# Power.net
KiCad netlist of a schematic drawn in Altium Designer
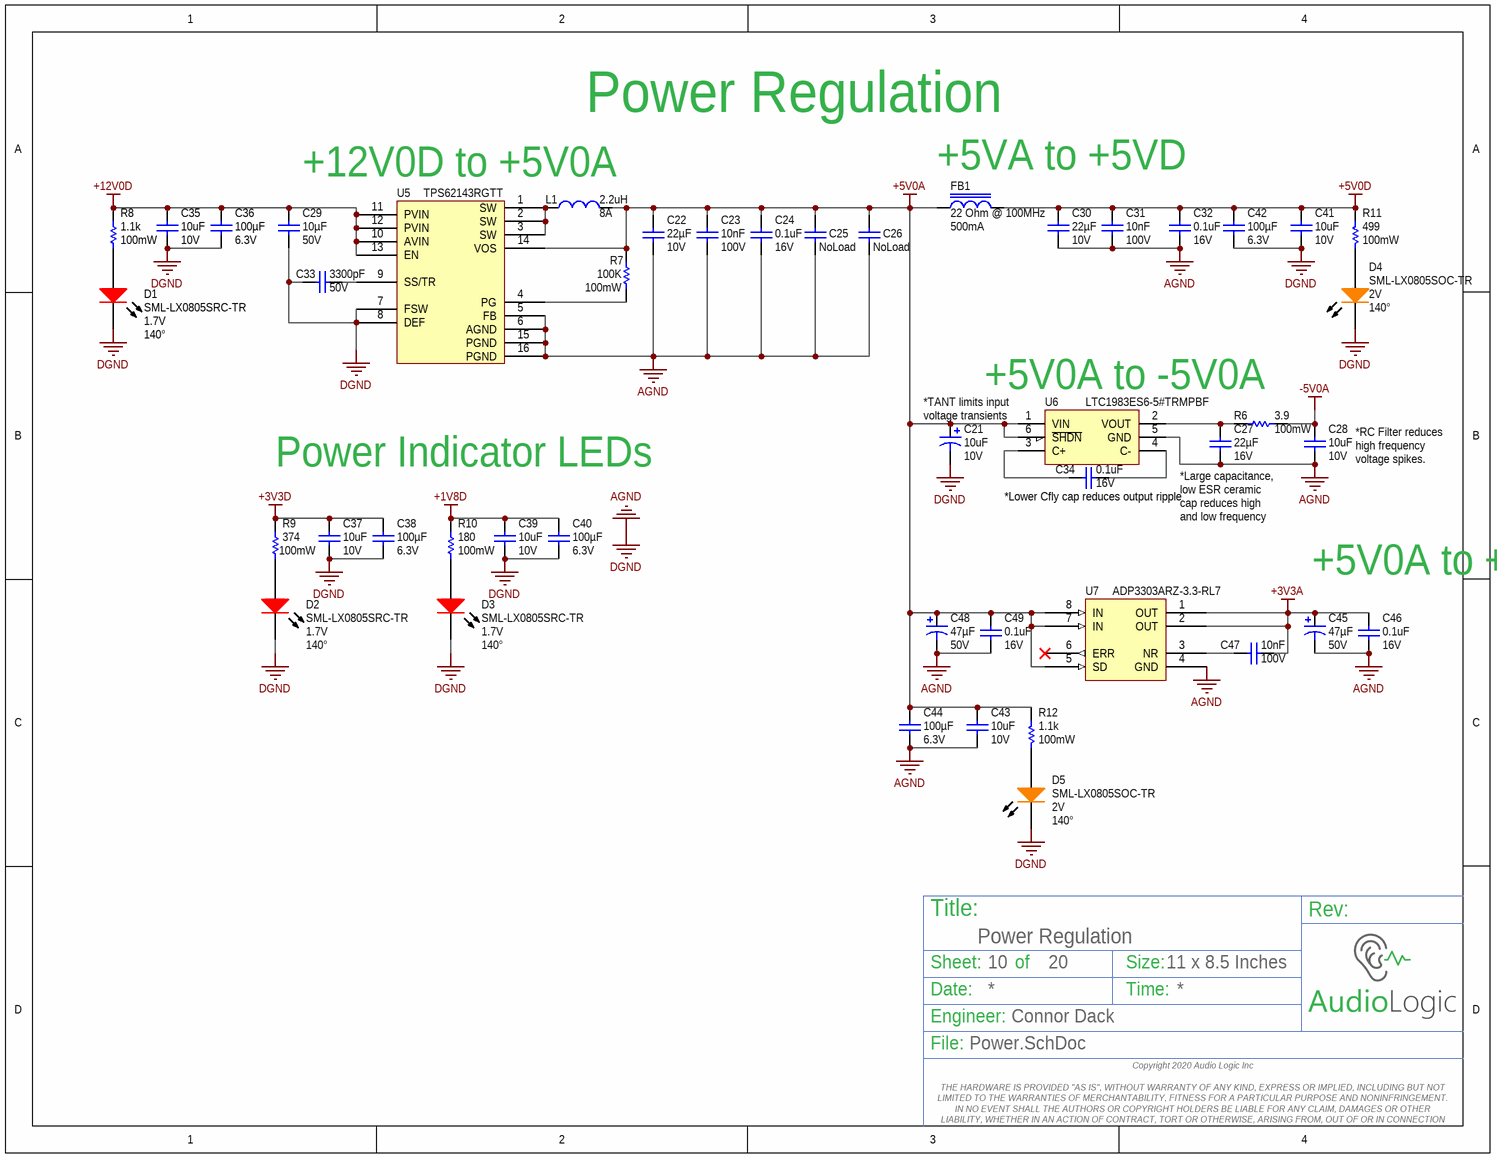
[diagram p0: Power.SchDoc]

(export (version "E")
  (design (tool "Eeschema 10.0.6"))
  (components
    (comp (ref "C21")
      (value "TR3A106K010C0900")
      (footprint "C1206_TANT")
      (description "CAP TANT 10UF 10V 10% 1206")
      (fields
        (field (name "MANUFACTURER") "Vishay Sprague")
        (field (name "TOLERANCE") "10%")
        (field (name "VOLTAGE") "10V")
        (field (name "CAPACITANCE") "10uF")
      )
      (libsource (lib "Schematic_Components_CD") (part "TR3A106K010C0900"))
    )
    (comp (ref "C22")
      (value "CL21A226KPCLRNC")
      (footprint "6-0805_L")
      (description "CAP CER 22UF 10V X5R 0805")
      (fields
        (field (name "MANUFACTURER") "Samsung Electro-Mechanics America, Inc.")
        (field (name "TOLERANCE") "±10%")
        (field (name "VOLTAGE - RATED") "10V")
        (field (name "CAPACITANCE") "22µF")
      )
      (libsource (lib "Schematic_Components") (part "CL21A226KPCLRNC"))
    )
    (comp (ref "C23")
      (value "C1608X8R2A103K080AA")
      (footprint "3-0603_L")
      (description "CAP CER 10000PF 100V X8R 0603")
      (fields
        (field (name "MANUFACTURER") "TDK")
        (field (name "VOLTAGE RATING") "100V")
        (field (name "TOLERANCE") "10%")
        (field (name "CAPACITANCE") "10nF")
      )
      (libsource (lib "Schematic_Components_CD") (part "C1608X8R2A103K080AA"))
    )
    (comp (ref "C24")
      (value "CL10F104ZO8NNNC")
      (footprint "3-0603_L")
      (description "CAP CER 0.1UF 16V Y5V 0603")
      (fields
        (field (name "MANUFACTURER") "Samsung")
        (field (name "TOLERANCE") "80%")
        (field (name "VOLTAGE RATING") "16V")
        (field (name "CAPACITANCE") "0.1uF")
      )
      (libsource (lib "Schematic_Components_CD") (part "CL10F104ZO8NNNC"))
    )
    (comp (ref "C25")
      (value "CAP 0603")
      (footprint "3-0603_L")
      (description "CAP 0603 SMD - NoLoad")
      (fields (field (name "CAPACITANCE") "NoLoad"))
      (libsource (lib "Schematic_Components_CD") (part "CAP 0603"))
    )
    (comp (ref "C26")
      (value "CAP 0603")
      (footprint "3-0603_L")
      (description "CAP 0603 SMD - NoLoad")
      (fields (field (name "CAPACITANCE") "NoLoad"))
      (libsource (lib "Schematic_Components_CD") (part "CAP 0603"))
    )
    (comp (ref "C27")
      (value "C3216X6S1C226M")
      (footprint "C1206")
      (description "CAP CER 22UF 16V 20% X6S 1206")
      (fields
        (field (name "MANUFACTURER") "TDK Corporation")
        (field (name "VOLTAGE - RATED") "16V")
        (field (name "TOLERANCE") "±20%")
        (field (name "CAPACITANCE") "22µF")
      )
      (libsource (lib "Schematic_Components") (part "C3216X6S1C226M"))
    )
    (comp (ref "C28")
      (value "GRM188R61A106ME69D")
      (footprint "3-0603_L")
      (description "CAP CER 10UF 10V X5R 0603")
      (fields
        (field (name "MANUFACTURER") "Murata")
        (field (name "TOLERANCE") "20%")
        (field (name "VOLTAGE RATING") "10V")
        (field (name "CAPACITANCE") "10uF")
      )
      (libsource (lib "Schematic_Components_CD") (part "GRM188R61A106ME69D"))
    )
    (comp (ref "C29")
      (value "C3216X5R1H106K")
      (footprint "C1206")
      (description "CAP CER 10UF 50V 10% X5R 1206")
      (fields
        (field (name "MANUFACTURER") "TDK Corporation")
        (field (name "VOLTAGE - RATED") "50V")
        (field (name "TOLERANCE") "±10%")
        (field (name "CAPACITANCE") "10µF")
      )
      (libsource (lib "Schematic_Components") (part "C3216X5R1H106K"))
    )
    (comp (ref "C30")
      (value "CL21A226KPCLRNC")
      (footprint "6-0805_L")
      (description "CAP CER 22UF 10V X5R 0805")
      (fields
        (field (name "MANUFACTURER") "Samsung Electro-Mechanics America, Inc.")
        (field (name "TOLERANCE") "±10%")
        (field (name "VOLTAGE - RATED") "10V")
        (field (name "CAPACITANCE") "22µF")
      )
      (libsource (lib "Schematic_Components") (part "CL21A226KPCLRNC"))
    )
    (comp (ref "C31")
      (value "C1608X8R2A103K080AA")
      (footprint "3-0603_L")
      (description "CAP CER 10000PF 100V X8R 0603")
      (fields
        (field (name "MANUFACTURER") "TDK")
        (field (name "VOLTAGE RATING") "100V")
        (field (name "TOLERANCE") "10%")
        (field (name "CAPACITANCE") "10nF")
      )
      (libsource (lib "Schematic_Components_CD") (part "C1608X8R2A103K080AA"))
    )
    (comp (ref "C32")
      (value "CL10F104ZO8NNNC")
      (footprint "3-0603_L")
      (description "CAP CER 0.1UF 16V Y5V 0603")
      (fields
        (field (name "MANUFACTURER") "Samsung")
        (field (name "TOLERANCE") "80%")
        (field (name "VOLTAGE RATING") "16V")
        (field (name "CAPACITANCE") "0.1uF")
      )
      (libsource (lib "Schematic_Components_CD") (part "CL10F104ZO8NNNC"))
    )
    (comp (ref "C33")
      (value "GRM2165C1H332JA01D")
      (footprint "6-0805_L")
      (description "CAP CER 3300PF 50V NP0 0805")
      (fields
        (field (name "MANUFACTURER") "Murata Electronics North America")
        (field (name "TOLERANCE") "±5%")
        (field (name "VOLTAGE - RATED") "50V")
        (field (name "CAPACITANCE") "3300pF")
      )
      (libsource (lib "Schematic_Components") (part "GRM2165C1H332JA01D"))
    )
    (comp (ref "C34")
      (value "CL10F104ZO8NNNC")
      (footprint "3-0603_L")
      (description "CAP CER 0.1UF 16V Y5V 0603")
      (fields
        (field (name "MANUFACTURER") "Samsung")
        (field (name "TOLERANCE") "80%")
        (field (name "VOLTAGE RATING") "16V")
        (field (name "CAPACITANCE") "0.1uF")
      )
      (libsource (lib "Schematic_Components_CD") (part "CL10F104ZO8NNNC"))
    )
    (comp (ref "C35")
      (value "GRM188R61A106ME69D")
      (footprint "3-0603_L")
      (description "CAP CER 10UF 10V X5R 0603")
      (fields
        (field (name "MANUFACTURER") "Murata")
        (field (name "TOLERANCE") "20%")
        (field (name "VOLTAGE RATING (DC)") "10V")
        (field (name "CAPACITANCE") "10uF")
      )
      (libsource (lib "Schematic_Components_CD") (part "GRM188R61A106ME69D"))
    )
    (comp (ref "C36")
      (value "CL32X107MQVNNNE")
      (footprint "C1210X25_L")
      (description "100µF 6.3V Ceramic Capacitor X6S 1210 (3225 Metric) 0.126\" L x 0.098\" W (3.20mm x 2.50mm)")
      (fields
        (field (name "MANUFACTURER") "Samsung Electro-Mechanics America, Inc.")
        (field (name "TOLERANCE") "±20%")
        (field (name "VOLTAGE - RATED") "6.3V")
        (field (name "CAPACITANCE") "100µF")
      )
      (libsource (lib "Schematic_Components") (part "CL32X107MQVNNNE"))
    )
    (comp (ref "C37")
      (value "GRM188R61A106ME69D")
      (footprint "3-0603_L")
      (description "CAP CER 10UF 10V X5R 0603")
      (fields
        (field (name "MANUFACTURER") "Murata")
        (field (name "TOLERANCE") "20%")
        (field (name "VOLTAGE RATING") "10V")
        (field (name "CAPACITANCE") "10uF")
      )
      (libsource (lib "Schematic_Components_CD") (part "GRM188R61A106ME69D"))
    )
    (comp (ref "C38")
      (value "CL32X107MQVNNNE")
      (footprint "C1210X25_L")
      (description "100µF 6.3V Ceramic Capacitor X6S 1210 (3225 Metric) 0.126\" L x 0.098\" W (3.20mm x 2.50mm)")
      (fields
        (field (name "MANUFACTURER") "Samsung Electro-Mechanics America, Inc.")
        (field (name "TOLERANCE") "±20%")
        (field (name "VOLTAGE - RATED") "6.3V")
        (field (name "CAPACITANCE") "100µF")
      )
      (libsource (lib "Schematic_Components") (part "CL32X107MQVNNNE"))
    )
    (comp (ref "C39")
      (value "GRM188R61A106ME69D")
      (footprint "3-0603_L")
      (description "CAP CER 10UF 10V X5R 0603")
      (fields
        (field (name "MANUFACTURER") "Murata")
        (field (name "TOLERANCE") "20%")
        (field (name "VOLTAGE RATING") "10V")
        (field (name "CAPACITANCE") "10uF")
      )
      (libsource (lib "Schematic_Components_CD") (part "GRM188R61A106ME69D"))
    )
    (comp (ref "C40")
      (value "CL32X107MQVNNNE")
      (footprint "C1210X25_L")
      (description "100µF 6.3V Ceramic Capacitor X6S 1210 (3225 Metric) 0.126\" L x 0.098\" W (3.20mm x 2.50mm)")
      (fields
        (field (name "MANUFACTURER") "Samsung Electro-Mechanics America, Inc.")
        (field (name "TOLERANCE") "±20%")
        (field (name "VOLTAGE - RATED") "6.3V")
        (field (name "CAPACITANCE") "100µF")
      )
      (libsource (lib "Schematic_Components") (part "CL32X107MQVNNNE"))
    )
    (comp (ref "C41")
      (value "GRM188R61A106ME69D")
      (footprint "3-0603_L")
      (description "CAP CER 10UF 10V X5R 0603")
      (fields
        (field (name "MANUFACTURER") "Murata")
        (field (name "TOLERANCE") "20%")
        (field (name "VOLTAGE RATING") "10V")
        (field (name "CAPACITANCE") "10uF")
      )
      (libsource (lib "Schematic_Components_CD") (part "GRM188R61A106ME69D"))
    )
    (comp (ref "C42")
      (value "CL32X107MQVNNNE")
      (footprint "C1210X25_L")
      (description "100µF 6.3V Ceramic Capacitor X6S 1210 (3225 Metric) 0.126\" L x 0.098\" W (3.20mm x 2.50mm)")
      (fields
        (field (name "MANUFACTURER") "Samsung Electro-Mechanics America, Inc.")
        (field (name "TOLERANCE") "±20%")
        (field (name "VOLTAGE - RATED") "6.3V")
        (field (name "CAPACITANCE") "100µF")
      )
      (libsource (lib "Schematic_Components") (part "CL32X107MQVNNNE"))
    )
    (comp (ref "C43")
      (value "GRM188R61A106ME69D")
      (footprint "3-0603_L")
      (description "CAP CER 10UF 10V X5R 0603")
      (fields
        (field (name "MANUFACTURER") "Murata")
        (field (name "TOLERANCE") "20%")
        (field (name "VOLTAGE RATING") "10V")
        (field (name "CAPACITANCE") "10uF")
      )
      (libsource (lib "Schematic_Components_CD") (part "GRM188R61A106ME69D"))
    )
    (comp (ref "C44")
      (value "CL32X107MQVNNNE")
      (footprint "C1210X25_L")
      (description "100µF 6.3V Ceramic Capacitor X6S 1210 (3225 Metric) 0.126\" L x 0.098\" W (3.20mm x 2.50mm)")
      (fields
        (field (name "MANUFACTURER") "Samsung Electro-Mechanics America, Inc.")
        (field (name "TOLERANCE") "±20%")
        (field (name "VOLTAGE - RATED") "6.3V")
        (field (name "CAPACITANCE") "100µF")
      )
      (libsource (lib "Schematic_Components") (part "CL32X107MQVNNNE"))
    )
    (comp (ref "C45")
      (value "EEE-FT1H470AP")
      (footprint "ALUMCAPC630D_D")
      (description "CAP ALUM 47UF 50V 20% SMD")
      (fields
        (field (name "MANUFACTURER") "Panasonic - ECG")
        (field (name "VOLTAGE RATING") "50V")
        (field (name "TOLERANCE") "±20%")
        (field (name "CAPACITANCE") "47µF")
      )
      (libsource (lib "Schematic_Components") (part "EEE-FT1H470AP"))
    )
    (comp (ref "C46")
      (value "CL10F104ZO8NNNC")
      (footprint "3-0603_L")
      (description "CAP CER 0.1UF 16V Y5V 0603")
      (fields
        (field (name "MANUFACTURER") "Samsung")
        (field (name "TOLERANCE") "80%")
        (field (name "VOLTAGE RATING") "16V")
        (field (name "CAPACITANCE") "0.1uF")
      )
      (libsource (lib "Schematic_Components_CD") (part "CL10F104ZO8NNNC"))
    )
    (comp (ref "C47")
      (value "C1608X8R2A103K080AA")
      (footprint "3-0603_L")
      (description "CAP CER 10000PF 100V X8R 0603")
      (fields
        (field (name "MANUFACTURER") "TDK")
        (field (name "VOLTAGE RATING") "100V")
        (field (name "TOLERANCE") "10%")
        (field (name "CAPACITANCE") "10nF")
      )
      (libsource (lib "Schematic_Components_CD") (part "C1608X8R2A103K080AA"))
    )
    (comp (ref "C48")
      (value "EEE-FT1H470AP")
      (footprint "ALUMCAPC630D_D")
      (description "CAP ALUM 47UF 50V 20% SMD")
      (fields
        (field (name "MANUFACTURER") "Panasonic - ECG")
        (field (name "VOLTAGE RATING") "50V")
        (field (name "TOLERANCE") "±20%")
        (field (name "CAPACITANCE") "47µF")
      )
      (libsource (lib "Schematic_Components") (part "EEE-FT1H470AP"))
    )
    (comp (ref "C49")
      (value "CL10F104ZO8NNNC")
      (footprint "3-0603_L")
      (description "CAP CER 0.1UF 16V Y5V 0603")
      (fields
        (field (name "MANUFACTURER") "Samsung")
        (field (name "TOLERANCE") "80%")
        (field (name "VOLTAGE RATING") "16V")
        (field (name "CAPACITANCE") "0.1uF")
      )
      (libsource (lib "Schematic_Components_CD") (part "CL10F104ZO8NNNC"))
    )
    (comp (ref "D1")
      (value "LED_RED 4")
      (footprint "DIOM2012X12L_RED")
      (description "LED 660NM SUPER RED CLR 0805 T/R")
      (fields
        (field (name "MANUFACTURER") "Lumex Opto/Components Inc")
        (field (name "MANUFACTURER PART NUMBER") "SML-LX0805SRC-TR")
        (field (name "VOLTAGE - FORWARD (VF) (TYP)") "1.7V")
        (field (name "VIEWING ANGLE") "140°")
      )
      (libsource (lib "Schematic_Components") (part "LED_RED 4"))
    )
    (comp (ref "D2")
      (value "LED_RED 4")
      (footprint "DIOM2012X12L_RED")
      (description "LED 660NM SUPER RED CLR 0805 T/R")
      (fields
        (field (name "MANUFACTURER") "Lumex Opto/Components Inc")
        (field (name "MANUFACTURER PART NUMBER") "SML-LX0805SRC-TR")
        (field (name "VOLTAGE - FORWARD (VF) (TYP)") "1.7V")
        (field (name "VIEWING ANGLE") "140°")
      )
      (libsource (lib "Schematic_Components") (part "LED_RED 4"))
    )
    (comp (ref "D3")
      (value "LED_RED 4")
      (footprint "DIOM2012X12L_RED")
      (description "LED 660NM SUPER RED CLR 0805 T/R")
      (fields
        (field (name "MANUFACTURER") "Lumex Opto/Components Inc")
        (field (name "MANUFACTURER PART NUMBER") "SML-LX0805SRC-TR")
        (field (name "VOLTAGE - FORWARD (VF) (TYP)") "1.7V")
        (field (name "VIEWING ANGLE") "140°")
      )
      (libsource (lib "Schematic_Components") (part "LED_RED 4"))
    )
    (comp (ref "D4")
      (value "LED_ORANGE 3")
      (footprint "DIOM2012X12L_ORANGE")
      (description "LED 610NM SUPER ORANGE 0805 SMD")
      (fields
        (field (name "MANUFACTURER") "Lumex Opto/Components Inc")
        (field (name "MANUFACTURER PART NUMBER") "SML-LX0805SOC-TR")
        (field (name "VOLTAGE - FORWARD (VF) (TYP)") "2V")
        (field (name "VIEWING ANGLE") "140°")
      )
      (libsource (lib "Schematic_Components") (part "LED_ORANGE 3"))
    )
    (comp (ref "D5")
      (value "LED_ORANGE 3")
      (footprint "DIOM2012X12L_ORANGE")
      (description "LED 610NM SUPER ORANGE 0805 SMD")
      (fields
        (field (name "MANUFACTURER") "Lumex Opto/Components Inc")
        (field (name "MANUFACTURER PART NUMBER") "SML-LX0805SOC-TR")
        (field (name "VOLTAGE - FORWARD (VF) (TYP)") "2V")
        (field (name "VIEWING ANGLE") "140°")
      )
      (libsource (lib "Schematic_Components") (part "LED_ORANGE 3"))
    )
    (comp (ref "FB1")
      (value "BLM18BA220SN1D")
      (footprint "3-0603_L")
      (description "FERRITE CHIP 22 OHM 500MA 0603")
      (fields
        (field (name "MANUFACTURER") "Murata Electronics North America")
        (field (name "CURRENT RATING") "500mA")
        (field (name "IMPEDANCE @ FREQUENCY") "22 Ohm @ 100MHz")
      )
      (libsource (lib "Schematic_Components") (part "BLM18BA220SN1D"))
    )
    (comp (ref "L1")
      (value "2.2uH Ind")
      (footprint "XFL4020")
      (description "Fixed Inductors XFL4020 AEC-Q200 2.2 uH 20 % 8 A")
      (fields
        (field (name "MANUFACTURER") "Coilcraft")
        (field (name "TOLERANCE") "20%")
        (field (name "MAX DC CURRENT") "8A")
        (field (name "INDUCTANCE") "2.2uH")
      )
      (libsource (lib "Schematic_Components_CD") (part "XFL4020-222MEB"))
    )
    (comp (ref "R6")
      (value "ERJ-3RQF3R9V")
      (footprint "3-0603_R_L")
      (description "RES 3.9 OHM 1/10W 1% 0603 SMD")
      (fields
        (field (name "MANUFACTURER") "Panasonic Electronic Components")
        (field (name "TOLERANCE") "±1%")
        (field (name "POWER (WATTS)") "100mW")
        (field (name "RESISTANCE (OHMS)") "3.9")
      )
      (libsource (lib "Schematic_Components") (part "ERJ-3RQF3R9V"))
    )
    (comp (ref "R7")
      (value "ERJ-3EKF1003V")
      (footprint "3-0603_R_L")
      (description "RES 100K OHM 1/10W 1% 0603 SMD")
      (fields
        (field (name "MANUFACTURER") "Panasonic - ECG")
        (field (name "POWER (WATTS)") "100mW")
        (field (name "TOLERANCE") "±1%")
        (field (name "RESISTANCE (OHMS)") "100K")
      )
      (libsource (lib "Schematic_Components") (part "ERJ-3EKF1003V"))
    )
    (comp (ref "R8")
      (value "RMCF0603FT1K10")
      (footprint "3-0603_R_L")
      (description "RES 1.1K OHM 1% 1/10W 0603")
      (fields
        (field (name "MANUFACTURER") "Stackpole Electronics")
        (field (name "POWER RATING") "100mW")
        (field (name "TOLERANCE") "1%")
        (field (name "RESISTANCE") "1.1k")
      )
      (libsource (lib "Schematic_Components_CD") (part "RMCF0603FT1K10"))
    )
    (comp (ref "R9")
      (value "ERJ-3EKF3740V")
      (footprint "3-0603_R_L")
      (description "RES SMD 374 OHM 1% 1/10W 0603")
      (fields
        (field (name "MANUFACTURER") "Panasonic Electronic Components")
        (field (name "TOLERANCE") "±1%")
        (field (name "POWER (WATTS)") "100mW")
        (field (name "RESISTANCE (OHMS)") "374")
      )
      (libsource (lib "Schematic_Components") (part "ERJ-3EKF3740V"))
    )
    (comp (ref "R10")
      (value "ERA-3AEB181V")
      (footprint "3-0603_R_L")
      (description "RES SMD 180 OHM 0.1% 1/10W 0603")
      (fields
        (field (name "MANUFACTURER") "Panasonic")
        (field (name "MANUFACTURER PART NUMBER") "ERA3AEB181V")
        (field (name "POWER RATING") "100mW")
        (field (name "RESISTANCE") "180")
      )
      (libsource (lib "Schematic_Components_CD") (part "ERA-3AEB181V"))
    )
    (comp (ref "R11")
      (value "ERJ-3EKF4990V")
      (footprint "3-0603_R_L")
      (description "RES 499 OHM 1/10W 1% 0603 SMD")
      (fields
        (field (name "MANUFACTURER") "Panasonic - ECG")
        (field (name "POWER (WATTS)") "100mW")
        (field (name "TOLERANCE") "±1%")
        (field (name "RESISTANCE (OHMS)") "499")
      )
      (libsource (lib "Schematic_Components") (part "ERJ-3EKF4990V"))
    )
    (comp (ref "R12")
      (value "RMCF0603FT1K10")
      (footprint "3-0603_R_L")
      (description "RES 1.1K OHM 1% 1/10W 0603")
      (fields
        (field (name "MANUFACTURER") "Stackpole Electronics")
        (field (name "POWER RATING") "100mW")
        (field (name "TOLERANCE") "1%")
        (field (name "RESISTANCE") "1.1k")
      )
      (libsource (lib "Schematic_Components_CD") (part "RMCF0603FT1K10"))
    )
    (comp (ref "U5")
      (value "IC REG BUCK 5V 2A SYNC 16QFN")
      (footprint "QFN50P300X300X100_HS-17N")
      (description "Buck Switching Regulator IC Positive Fixed 5V 1 Output 2A 16-VFQFN Exposed Pad")
      (fields
        (field (name "MANUFACTURER") "Texas Instruments")
        (field (name "MANUFACTURER PART NUMBER") "TPS62143RGTT")
      )
      (libsource (lib "Schematic_Components_CD") (part "TPS62143RGTT"))
    )
    (comp (ref "U6")
      (value "~")
      (footprint "SOT23-6_L")
      (description "IC REG SWITCHD CAP INV -5V SOT23")
      (fields
        (field (name "MANUFACTURER") "Linear Technology")
        (field (name "MANUFACTURER PART NUMBER") "LTC1983ES6-5#TRMPBF")
      )
      (libsource (lib "Schematic_Components") (part "LTC1983ES6-5#TRMPBF"))
    )
    (comp (ref "U7")
      (value "ADP3303ARZ-3.3-RL7")
      (footprint "SOIC127P600X175-8L")
      (description "Linear Voltage Regulator IC Positive Fixed 1 Output 3.3V 200mA 8-SOIC")
      (fields
        (field (name "MANUFACTURER") "Analog Devices Inc.")
        (field (name "MANUFACTURER PART NUMBER") "ADP3303ARZ-3.3-RL7")
      )
      (libsource (lib "NIH_DE0_Nano_Daughter_Card_Library") (part "ADP3303ARZ-3.3-RL7"))
    )
  )
  (nets
    (net (code "1") (name "+1V8D") (class "Default")
      (node (ref "C39") (pin "2") (pinfunction "2_2") (pintype "passive"))
      (node (ref "C40") (pin "2") (pinfunction "2_2") (pintype "passive"))
      (node (ref "R10") (pin "2") (pinfunction "2_2") (pintype "passive"))
    )
    (net (code "2") (name "+3V3A") (class "Default")
      (node (ref "C45") (pin "1") (pinfunction "P_1") (pintype "passive"))
      (node (ref "C46") (pin "1") (pinfunction "1_1") (pintype "passive"))
      (node (ref "C47") (pin "1") (pinfunction "1_1") (pintype "passive"))
      (node (ref "U7") (pin "1") (pinfunction "OUT_1") (pintype "passive"))
      (node (ref "U7") (pin "2") (pinfunction "OUT_2") (pintype "passive"))
    )
    (net (code "3") (name "+3V3D") (class "Default")
      (node (ref "C37") (pin "2") (pinfunction "2_2") (pintype "passive"))
      (node (ref "C38") (pin "2") (pinfunction "2_2") (pintype "passive"))
      (node (ref "R9") (pin "2") (pinfunction "2_2") (pintype "passive"))
    )
    (net (code "4") (name "+5V0A") (class "Default")
      (node (ref "C21") (pin "1") (pinfunction "P_1") (pintype "passive"))
      (node (ref "C22") (pin "2") (pinfunction "2_2") (pintype "passive"))
      (node (ref "C23") (pin "2") (pinfunction "2_2") (pintype "passive"))
      (node (ref "C24") (pin "1") (pinfunction "1_1") (pintype "passive"))
      (node (ref "C25") (pin "2") (pinfunction "2_2") (pintype "passive"))
      (node (ref "C26") (pin "2") (pinfunction "2_2") (pintype "passive"))
      (node (ref "C43") (pin "2") (pinfunction "2_2") (pintype "passive"))
      (node (ref "C44") (pin "2") (pinfunction "2_2") (pintype "passive"))
      (node (ref "C48") (pin "1") (pinfunction "P_1") (pintype "passive"))
      (node (ref "C49") (pin "1") (pinfunction "1_1") (pintype "passive"))
      (node (ref "FB1") (pin "1") (pinfunction "1_1") (pintype "passive"))
      (node (ref "L1") (pin "2") (pinfunction "2_2") (pintype "passive"))
      (node (ref "R12") (pin "2") (pinfunction "2_2") (pintype "passive"))
      (node (ref "R7") (pin "2") (pinfunction "2_2") (pintype "passive"))
      (node (ref "U5") (pin "14") (pinfunction "VOS_14") (pintype "passive"))
      (node (ref "U6") (pin "1") (pinfunction "VIN_1") (pintype "power_in"))
      (node (ref "U6") (pin "6") (pinfunction "SHDN_6") (pintype "passive"))
      (node (ref "U7") (pin "5") (pinfunction "SD_5") (pintype "input"))
      (node (ref "U7") (pin "7") (pinfunction "IN_7") (pintype "input"))
      (node (ref "U7") (pin "8") (pinfunction "IN_8") (pintype "input"))
    )
    (net (code "5") (name "+5V0D") (class "Default")
      (node (ref "C30") (pin "2") (pinfunction "2_2") (pintype "passive"))
      (node (ref "C31") (pin "2") (pinfunction "2_2") (pintype "passive"))
      (node (ref "C32") (pin "1") (pinfunction "1_1") (pintype "passive"))
      (node (ref "C41") (pin "2") (pinfunction "2_2") (pintype "passive"))
      (node (ref "C42") (pin "2") (pinfunction "2_2") (pintype "passive"))
      (node (ref "FB1") (pin "2") (pinfunction "2_2") (pintype "passive"))
      (node (ref "R11") (pin "2") (pinfunction "2_2") (pintype "passive"))
    )
    (net (code "6") (name "+12V0D") (class "Default")
      (node (ref "C29") (pin "2") (pinfunction "2_2") (pintype "passive"))
      (node (ref "C35") (pin "2") (pinfunction "2_2") (pintype "passive"))
      (node (ref "C36") (pin "2") (pinfunction "2_2") (pintype "passive"))
      (node (ref "R8") (pin "2") (pinfunction "2_2") (pintype "passive"))
      (node (ref "U5") (pin "10") (pinfunction "AVIN_10") (pintype "passive"))
      (node (ref "U5") (pin "11") (pinfunction "PVIN_11") (pintype "passive"))
      (node (ref "U5") (pin "12") (pinfunction "PVIN_12") (pintype "passive"))
      (node (ref "U5") (pin "13") (pinfunction "EN_13") (pintype "passive"))
    )
    (net (code "7") (name "-5V0A") (class "Default")
      (node (ref "C28") (pin "2") (pinfunction "2_2") (pintype "passive"))
      (node (ref "R6") (pin "2") (pinfunction "2_2") (pintype "passive"))
    )
    (net (code "8") (name "AGND") (class "Default")
      (node (ref "C21") (pin "2") (pinfunction "N_2") (pintype "passive"))
      (node (ref "C22") (pin "1") (pinfunction "1_1") (pintype "passive"))
      (node (ref "C23") (pin "1") (pinfunction "1_1") (pintype "passive"))
      (node (ref "C24") (pin "2") (pinfunction "2_2") (pintype "passive"))
      (node (ref "C25") (pin "1") (pinfunction "1_1") (pintype "passive"))
      (node (ref "C26") (pin "1") (pinfunction "1_1") (pintype "passive"))
      (node (ref "C27") (pin "1") (pinfunction "1_1") (pintype "passive"))
      (node (ref "C28") (pin "1") (pinfunction "1_1") (pintype "passive"))
      (node (ref "C29") (pin "1") (pinfunction "1_1") (pintype "passive"))
      (node (ref "C30") (pin "1") (pinfunction "1_1") (pintype "passive"))
      (node (ref "C31") (pin "1") (pinfunction "1_1") (pintype "passive"))
      (node (ref "C32") (pin "2") (pinfunction "2_2") (pintype "passive"))
      (node (ref "C33") (pin "1") (pinfunction "1_1") (pintype "passive"))
      (node (ref "C35") (pin "1") (pinfunction "1_1") (pintype "passive"))
      (node (ref "C36") (pin "1") (pinfunction "1_1") (pintype "passive"))
      (node (ref "C37") (pin "1") (pinfunction "1_1") (pintype "passive"))
      (node (ref "C38") (pin "1") (pinfunction "1_1") (pintype "passive"))
      (node (ref "C39") (pin "1") (pinfunction "1_1") (pintype "passive"))
      (node (ref "C40") (pin "1") (pinfunction "1_1") (pintype "passive"))
      (node (ref "C41") (pin "1") (pinfunction "1_1") (pintype "passive"))
      (node (ref "C42") (pin "1") (pinfunction "1_1") (pintype "passive"))
      (node (ref "C43") (pin "1") (pinfunction "1_1") (pintype "passive"))
      (node (ref "C44") (pin "1") (pinfunction "1_1") (pintype "passive"))
      (node (ref "C45") (pin "2") (pinfunction "N_2") (pintype "passive"))
      (node (ref "C46") (pin "2") (pinfunction "2_2") (pintype "passive"))
      (node (ref "C48") (pin "2") (pinfunction "N_2") (pintype "passive"))
      (node (ref "C49") (pin "2") (pinfunction "2_2") (pintype "passive"))
      (node (ref "D1") (pin "2") (pinfunction "K_2") (pintype "passive"))
      (node (ref "D2") (pin "2") (pinfunction "K_2") (pintype "passive"))
      (node (ref "D3") (pin "2") (pinfunction "K_2") (pintype "passive"))
      (node (ref "D4") (pin "2") (pinfunction "K_2") (pintype "passive"))
      (node (ref "D5") (pin "2") (pinfunction "K_2") (pintype "passive"))
      (node (ref "U5") (pin "15") (pinfunction "PGND_15") (pintype "passive"))
      (node (ref "U5") (pin "16") (pinfunction "PGND_16") (pintype "passive"))
      (node (ref "U5") (pin "5") (pinfunction "FB_5") (pintype "passive"))
      (node (ref "U5") (pin "6") (pinfunction "AGND_6") (pintype "passive"))
      (node (ref "U5") (pin "7") (pinfunction "FSW_7") (pintype "passive"))
      (node (ref "U5") (pin "8") (pinfunction "DEF_8") (pintype "passive"))
      (node (ref "U6") (pin "5") (pinfunction "GND_5") (pintype "passive"))
      (node (ref "U7") (pin "4") (pinfunction "GND_4") (pintype "passive"))
    )
    (net (code "9") (name "Net-(D1-A)") (class "Default")
      (node (ref "D1") (pin "1") (pinfunction "A_1") (pintype "passive"))
      (node (ref "R8") (pin "1") (pinfunction "1_1") (pintype "passive"))
    )
    (net (code "10") (name "Net-(D2-A)") (class "Default")
      (node (ref "D2") (pin "1") (pinfunction "A_1") (pintype "passive"))
      (node (ref "R9") (pin "1") (pinfunction "1_1") (pintype "passive"))
    )
    (net (code "11") (name "Net-(D3-A)") (class "Default")
      (node (ref "D3") (pin "1") (pinfunction "A_1") (pintype "passive"))
      (node (ref "R10") (pin "1") (pinfunction "1_1") (pintype "passive"))
    )
    (net (code "12") (name "Net-(D4-A)") (class "Default")
      (node (ref "D4") (pin "1") (pinfunction "A_1") (pintype "passive"))
      (node (ref "R11") (pin "1") (pinfunction "1_1") (pintype "passive"))
    )
    (net (code "13") (name "Net-(D5-A)") (class "Default")
      (node (ref "D5") (pin "1") (pinfunction "A_1") (pintype "passive"))
      (node (ref "R12") (pin "1") (pinfunction "1_1") (pintype "passive"))
    )
    (net (code "14") (name "Net-(L1-Pad1)") (class "Default")
      (node (ref "L1") (pin "1") (pinfunction "1_1") (pintype "passive"))
      (node (ref "U5") (pin "1") (pinfunction "SW_1") (pintype "passive"))
      (node (ref "U5") (pin "2") (pinfunction "SW_2") (pintype "passive"))
      (node (ref "U5") (pin "3") (pinfunction "SW_3") (pintype "passive"))
    )
    (net (code "15") (name "Net-(U5-PG)") (class "Default")
      (node (ref "R7") (pin "1") (pinfunction "1_1") (pintype "passive"))
      (node (ref "U5") (pin "4") (pinfunction "PG_4") (pintype "passive"))
    )
    (net (code "16") (name "Net-(U5-SS{slash}TR)") (class "Default")
      (node (ref "C33") (pin "2") (pinfunction "2_2") (pintype "passive"))
      (node (ref "U5") (pin "9") (pinfunction "SS/TR_9") (pintype "passive"))
    )
    (net (code "17") (name "Net-(U6-C+)") (class "Default")
      (node (ref "C34") (pin "1") (pinfunction "1_1") (pintype "passive"))
      (node (ref "U6") (pin "3") (pinfunction "C+_3") (pintype "passive"))
    )
    (net (code "18") (name "Net-(U6-C-)") (class "Default")
      (node (ref "C34") (pin "2") (pinfunction "2_2") (pintype "passive"))
      (node (ref "U6") (pin "4") (pinfunction "C-_4") (pintype "passive"))
    )
    (net (code "19") (name "Net-(U6-VOUT)") (class "Default")
      (node (ref "C27") (pin "2") (pinfunction "2_2") (pintype "passive"))
      (node (ref "R6") (pin "1") (pinfunction "1_1") (pintype "passive"))
      (node (ref "U6") (pin "2") (pinfunction "VOUT_2") (pintype "power_in"))
    )
    (net (code "20") (name "Net-(U7-NR)") (class "Default")
      (node (ref "C47") (pin "2") (pinfunction "2_2") (pintype "passive"))
      (node (ref "U7") (pin "3") (pinfunction "NR_3") (pintype "passive"))
    )
    (net (code "21") (name "unconnected-(U7-ERR-Pad6)") (class "Default")
      (node (ref "U7") (pin "6") (pinfunction "ERR_6") (pintype "output+no_connect"))
    )
  )
)
